# POWER.net
KiCad netlist of a schematic drawn in Altium Designer
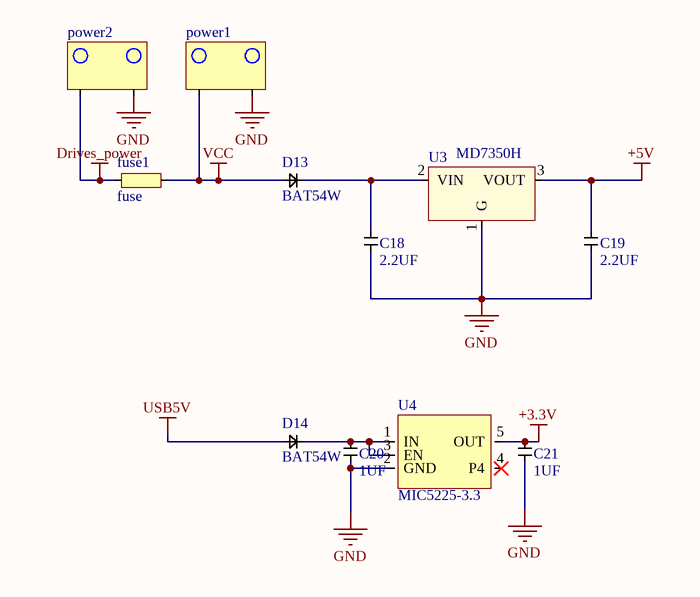
[diagram p0: POWER.SchDoc]

(export (version "E")
  (design (tool "Eeschema 10.0.6"))
  (components
    (comp (ref "C18") (value "2.2UF") (footprint "1206") (libsource (lib "jx") (part "C")))
    (comp (ref "C19") (value "2.2UF") (footprint "1206") (libsource (lib "jx") (part "C")))
    (comp (ref "C20") (value "1UF") (footprint "0603") (libsource (lib "jx") (part "C")))
    (comp (ref "C21") (value "1UF") (footprint "0603") (libsource (lib "jx") (part "C")))
    (comp (ref "D13")
      (value "BAT54W")
      (footprint "SOD-123")
      (description "BAT46W")
      (libsource (lib "jx") (part "Diode"))
    )
    (comp (ref "D14")
      (value "BAT54W")
      (footprint "SOD-123")
      (description "BAT46W")
      (libsource (lib "jx") (part "Diode"))
    )
    (comp (ref "fuse1") (value "fuse") (footprint "保险丝小号") (libsource (lib "jx") (part "fuse")))
    (comp (ref "power1")
      (value "KF-7.62-2P")
      (footprint "TERMINALBLOCK_BORNIER-2_P5.08MM_2")
      (libsource (lib "jx") (part "KF-7.62-2P"))
    )
    (comp (ref "power2")
      (value "KF-7.62-2P")
      (footprint "TERMINALBLOCK_BORNIER-2_P5.08MM_2")
      (libsource (lib "jx") (part "KF-7.62-2P"))
    )
    (comp (ref "U3") (value "MD7350H") (footprint "SOT-89") (libsource (lib "jx") (part "MD7350H")))
    (comp (ref "U4") (value "MIC5225-3.3") (footprint "SOT23-5") (libsource (lib "jx") (part "MIC5225-3.3")))
  )
  (nets
    (net (code "1") (name "+3.3V") (class "Default")
      (node (ref "C21") (pin "1") (pinfunction "1_1") (pintype "passive"))
      (node (ref "U4") (pin "5") (pinfunction "OUT_5") (pintype "passive"))
    )
    (net (code "2") (name "+5V") (class "Default")
      (node (ref "C19") (pin "1") (pinfunction "1_1") (pintype "passive"))
      (node (ref "U3") (pin "3") (pinfunction "VOUT_3") (pintype "passive"))
    )
    (net (code "3") (name "Drives_power") (class "Default")
      (node (ref "fuse1") (pin "1") (pinfunction "1_1") (pintype "passive"))
      (node (ref "power2") (pin "1") (pinfunction "1_1") (pintype "passive"))
    )
    (net (code "4") (name "GND") (class "Default")
      (node (ref "C18") (pin "2") (pinfunction "2_2") (pintype "passive"))
      (node (ref "C19") (pin "2") (pinfunction "2_2") (pintype "passive"))
      (node (ref "C20") (pin "2") (pinfunction "2_2") (pintype "passive"))
      (node (ref "C21") (pin "2") (pinfunction "2_2") (pintype "passive"))
      (node (ref "U3") (pin "1") (pinfunction "G_1") (pintype "passive"))
      (node (ref "U4") (pin "2") (pinfunction "GND_2") (pintype "passive"))
      (node (ref "power1") (pin "2") (pinfunction "2_2") (pintype "passive"))
      (node (ref "power2") (pin "2") (pinfunction "2_2") (pintype "passive"))
    )
    (net (code "5") (name "Net-(U3-VIN)") (class "Default")
      (node (ref "C18") (pin "1") (pinfunction "1_1") (pintype "passive"))
      (node (ref "D13") (pin "2") (pinfunction "2_2") (pintype "passive"))
      (node (ref "U3") (pin "2") (pinfunction "VIN_2") (pintype "passive"))
    )
    (net (code "6") (name "Net-(U4-EN)") (class "Default")
      (node (ref "C20") (pin "1") (pinfunction "1_1") (pintype "passive"))
      (node (ref "D14") (pin "2") (pinfunction "2_2") (pintype "passive"))
      (node (ref "U4") (pin "1") (pinfunction "IN_1") (pintype "passive"))
      (node (ref "U4") (pin "3") (pinfunction "EN_3") (pintype "passive"))
    )
    (net (code "7") (name "USB5V") (class "Default")
      (node (ref "D14") (pin "1") (pinfunction "1_1") (pintype "passive"))
    )
    (net (code "8") (name "VCC") (class "Default")
      (node (ref "D13") (pin "1") (pinfunction "1_1") (pintype "passive"))
      (node (ref "fuse1") (pin "2") (pinfunction "2_2") (pintype "passive"))
      (node (ref "power1") (pin "1") (pinfunction "1_1") (pintype "passive"))
    )
    (net (code "9") (name "unconnected-(U4-P4-Pad4)") (class "Default")
      (node (ref "U4") (pin "4") (pinfunction "P4_4") (pintype "passive+no_connect"))
    )
  )
)
